# SH1_-_STM32.net
KiCad netlist of a schematic drawn in Altium Designer
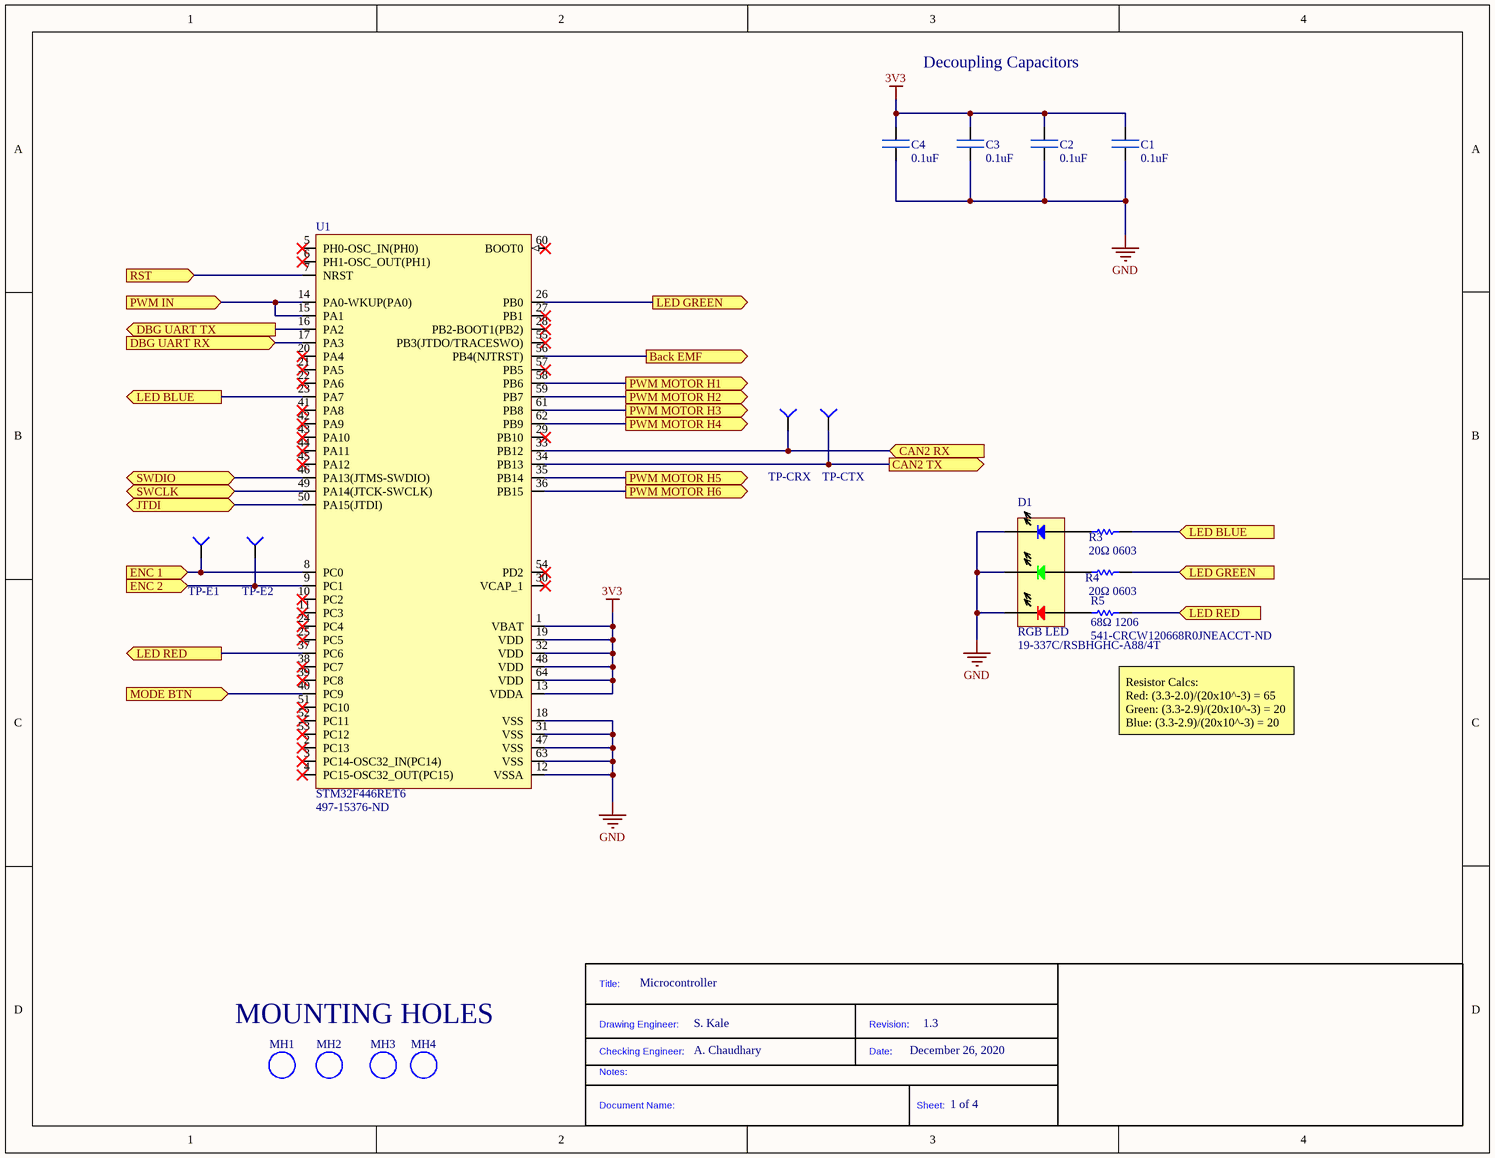
[diagram p0: SH1 - STM32.SchDoc]

(export (version "E")
  (design (tool "Eeschema 10.0.6"))
  (components
    (comp (ref "*") (value "HORNET LOGO") (libsource (lib "HORNET_MOTOR_CONTROLLER") (part "HORNET LOGO")))
    (comp (ref "C1")
      (value "0.1uF")
      (footprint "CAP0.1uF")
      (fields
        (field (name "MANUFACTURER") "Murata")
        (field (name "MANUFACTURER PART NUMBER") "GRM155R71C104KA88D")
      )
      (libsource (lib "AVRTank") (part "CAP 0.1uF"))
    )
    (comp (ref "C2")
      (value "0.1uF")
      (footprint "CAP0.1uF")
      (fields
        (field (name "MANUFACTURER") "Murata")
        (field (name "MANUFACTURER PART NUMBER") "GRM155R71C104KA88D")
      )
      (libsource (lib "AVRTank") (part "CAP 0.1uF"))
    )
    (comp (ref "C3")
      (value "0.1uF")
      (footprint "CAP0.1uF")
      (fields
        (field (name "MANUFACTURER") "Murata")
        (field (name "MANUFACTURER PART NUMBER") "GRM155R71C104KA88D")
      )
      (libsource (lib "AVRTank") (part "CAP 0.1uF"))
    )
    (comp (ref "C4")
      (value "0.1uF")
      (footprint "CAP0.1uF")
      (fields
        (field (name "MANUFACTURER") "Murata")
        (field (name "MANUFACTURER PART NUMBER") "GRM155R71C104KA88D")
      )
      (libsource (lib "AVRTank") (part "CAP 0.1uF"))
    )
    (comp (ref "D1")
      (value "RGB LED")
      (footprint "19-337C/RSBHGHC-A88/4T")
      (description "Tri Color Pcb Top View SMD Led R")
      (fields
        (field (name "MANUFACTURER") "Everlight")
        (field (name "MANUFACTURER PART NUMBER") "19-337C/RSBHGHC-A88/4T")
      )
      (libsource (lib "HORNET_MOTOR_CONTROLLER") (part "LED_RGB"))
    )
    (comp (ref "MH1")
      (value "MOUNTING HOLE")
      (footprint "MOUNTING HOLE")
      (libsource (lib "HORNET_MOTOR_CONTROLLER") (part "MOUNTING HOLE"))
    )
    (comp (ref "MH2")
      (value "MOUNTING HOLE")
      (footprint "MOUNTING HOLE")
      (libsource (lib "HORNET_MOTOR_CONTROLLER") (part "MOUNTING HOLE"))
    )
    (comp (ref "MH3")
      (value "MOUNTING HOLE")
      (footprint "MOUNTING HOLE")
      (libsource (lib "HORNET_MOTOR_CONTROLLER") (part "MOUNTING HOLE"))
    )
    (comp (ref "MH4")
      (value "MOUNTING HOLE")
      (footprint "MOUNTING HOLE")
      (libsource (lib "HORNET_MOTOR_CONTROLLER") (part "MOUNTING HOLE"))
    )
    (comp (ref "R3")
      (value "20Ω 0603")
      (footprint "SDR03EZPJ200")
      (description "Fixed Resistor, 0.1W, 20ohm, 50V, 5% +/-Tol, 200ppm/Cel, Surface Mount, 0603")
      (fields (field (name "MANUFACTURER") "Rohm") (field (name "MANUFACTURER PART NUMBER") "SDR03EZPJ200"))
      (libsource (lib "HORNET_MOTOR_CONTROLLER") (part "RES 20Ω"))
    )
    (comp (ref "R4")
      (value "20Ω 0603")
      (footprint "SDR03EZPJ200")
      (description "Fixed Resistor, 0.1W, 20ohm, 50V, 5% +/-Tol, 200ppm/Cel, Surface Mount, 0603")
      (fields (field (name "MANUFACTURER") "Rohm") (field (name "MANUFACTURER PART NUMBER") "SDR03EZPJ200"))
      (libsource (lib "HORNET_MOTOR_CONTROLLER") (part "RES 20Ω"))
    )
    (comp (ref "R5")
      (value "68Ω 1206")
      (footprint "CRCW120668R0JNEAC")
      (description "VISCRCW120668R0JNEAC Res Thick Film 1206")
      (fields
        (field (name "MANUFACTURER") "Vishay")
        (field (name "MANUFACTURER PART NUMBER") "CRCW120668R0JNEAC")
        (field (name "SUPPLIER PART NUMBER 1") "541-CRCW120668R0JNEACCT-ND")
      )
      (libsource (lib "HORNET_MOTOR_CONTROLLER") (part "RES 68Ω"))
    )
    (comp (ref "TP-CRX")
      (value "TESTPT")
      (footprint "TESTPT SQUARE")
      (libsource (lib "HORNET_MOTOR_CONTROLLER") (part "TESTPT SQUARE"))
    )
    (comp (ref "TP-CTX")
      (value "TESTPT")
      (footprint "TESTPT SQUARE")
      (libsource (lib "HORNET_MOTOR_CONTROLLER") (part "TESTPT SQUARE"))
    )
    (comp (ref "TP-E1")
      (value "TESTPT")
      (footprint "TESTPT SQUARE")
      (libsource (lib "HORNET_MOTOR_CONTROLLER") (part "TESTPT SQUARE"))
    )
    (comp (ref "TP-E2")
      (value "TESTPT")
      (footprint "TESTPT SQUARE")
      (libsource (lib "HORNET_MOTOR_CONTROLLER") (part "TESTPT SQUARE"))
    )
    (comp (ref "U1")
      (value "STM32F446RET6")
      (footprint "STM_LQFP64_N")
      (description "RISC Microcontroller, 32-Bit, FLASH, CORTEX-M4F CPU, 180MHz, CMOS, PQFP64")
      (fields
        (field (name "MANUFACTURER") "STMicroelectronics")
        (field (name "SUPPLIER PART NUMBER 1") "497-15376-ND")
      )
      (libsource (lib "HORNET_MOTOR_CONTROLLER") (part "STM32F446RET6"))
    )
  )
  (nets
    (net (code "1") (name "/Back EMF") (class "Default")
      (node (ref "U1") (pin "56") (pinfunction "PB4(NJTRST)_56") (pintype "bidirectional"))
    )
    (net (code "2") (name "/CAN2 RX") (class "Default")
      (node (ref "TP-CRX") (pin "1") (pinfunction "=value_1") (pintype "passive"))
      (node (ref "U1") (pin "33") (pinfunction "PB12_33") (pintype "bidirectional"))
    )
    (net (code "3") (name "/CAN2 TX") (class "Default")
      (node (ref "TP-CTX") (pin "1") (pinfunction "=value_1") (pintype "passive"))
      (node (ref "U1") (pin "34") (pinfunction "PB13_34") (pintype "bidirectional"))
    )
    (net (code "4") (name "/DBG UART RX") (class "Default")
      (node (ref "U1") (pin "17") (pinfunction "PA3_17") (pintype "bidirectional"))
    )
    (net (code "5") (name "/DBG UART TX") (class "Default")
      (node (ref "U1") (pin "16") (pinfunction "PA2_16") (pintype "bidirectional"))
    )
    (net (code "6") (name "/ENC 1") (class "Default")
      (node (ref "TP-E1") (pin "1") (pinfunction "=value_1") (pintype "passive"))
      (node (ref "U1") (pin "8") (pinfunction "PC0_8") (pintype "bidirectional"))
    )
    (net (code "7") (name "/ENC 2") (class "Default")
      (node (ref "TP-E2") (pin "1") (pinfunction "=value_1") (pintype "passive"))
      (node (ref "U1") (pin "9") (pinfunction "PC1_9") (pintype "bidirectional"))
    )
    (net (code "8") (name "/JTDI") (class "Default")
      (node (ref "U1") (pin "50") (pinfunction "PA15(JTDI)_50") (pintype "bidirectional"))
    )
    (net (code "9") (name "/LED BLUE") (class "Default")
      (node (ref "R3") (pin "2") (pinfunction "2_2") (pintype "passive"))
      (node (ref "U1") (pin "23") (pinfunction "PA7_23") (pintype "bidirectional"))
    )
    (net (code "10") (name "/LED GREEN") (class "Default")
      (node (ref "R4") (pin "2") (pinfunction "2_2") (pintype "passive"))
      (node (ref "U1") (pin "26") (pinfunction "PB0_26") (pintype "bidirectional"))
    )
    (net (code "11") (name "/LED RED") (class "Default")
      (node (ref "R5") (pin "2") (pinfunction "2_2") (pintype "passive"))
      (node (ref "U1") (pin "37") (pinfunction "PC6_37") (pintype "bidirectional"))
    )
    (net (code "12") (name "/MODE BTN") (class "Default")
      (node (ref "U1") (pin "40") (pinfunction "PC9_40") (pintype "bidirectional"))
    )
    (net (code "13") (name "/PWM IN") (class "Default")
      (node (ref "U1") (pin "14") (pinfunction "PA0-WKUP(PA0)_14") (pintype "bidirectional"))
      (node (ref "U1") (pin "15") (pinfunction "PA1_15") (pintype "bidirectional"))
    )
    (net (code "14") (name "/PWM MOTOR H1") (class "Default")
      (node (ref "U1") (pin "58") (pinfunction "PB6_58") (pintype "bidirectional"))
    )
    (net (code "15") (name "/PWM MOTOR H2") (class "Default")
      (node (ref "U1") (pin "59") (pinfunction "PB7_59") (pintype "bidirectional"))
    )
    (net (code "16") (name "/PWM MOTOR H3") (class "Default")
      (node (ref "U1") (pin "61") (pinfunction "PB8_61") (pintype "bidirectional"))
    )
    (net (code "17") (name "/PWM MOTOR H4") (class "Default")
      (node (ref "U1") (pin "62") (pinfunction "PB9_62") (pintype "bidirectional"))
    )
    (net (code "18") (name "/PWM MOTOR H5") (class "Default")
      (node (ref "U1") (pin "35") (pinfunction "PB14_35") (pintype "bidirectional"))
    )
    (net (code "19") (name "/PWM MOTOR H6") (class "Default")
      (node (ref "U1") (pin "36") (pinfunction "PB15_36") (pintype "bidirectional"))
    )
    (net (code "20") (name "/RST") (class "Default")
      (node (ref "U1") (pin "7") (pinfunction "NRST_7") (pintype "bidirectional"))
    )
    (net (code "21") (name "/SWCLK") (class "Default")
      (node (ref "U1") (pin "49") (pinfunction "PA14(JTCK-SWCLK)_49") (pintype "bidirectional"))
    )
    (net (code "22") (name "/SWDIO") (class "Default")
      (node (ref "U1") (pin "46") (pinfunction "PA13(JTMS-SWDIO)_46") (pintype "bidirectional"))
    )
    (net (code "23") (name "3V3") (class "Default")
      (node (ref "C1") (pin "2") (pinfunction "08_2") (pintype "passive"))
      (node (ref "C2") (pin "2") (pinfunction "08_2") (pintype "passive"))
      (node (ref "C3") (pin "2") (pinfunction "08_2") (pintype "passive"))
      (node (ref "C4") (pin "2") (pinfunction "08_2") (pintype "passive"))
      (node (ref "U1") (pin "1") (pinfunction "VBAT_1") (pintype "power_in"))
      (node (ref "U1") (pin "13") (pinfunction "VDDA_13") (pintype "power_in"))
      (node (ref "U1") (pin "19") (pinfunction "VDD_19") (pintype "power_in"))
      (node (ref "U1") (pin "32") (pinfunction "VDD_32") (pintype "power_in"))
      (node (ref "U1") (pin "48") (pinfunction "VDD_48") (pintype "power_in"))
      (node (ref "U1") (pin "64") (pinfunction "VDD_64") (pintype "power_in"))
    )
    (net (code "24") (name "GND") (class "Default")
      (node (ref "C1") (pin "1") (pintype "passive"))
      (node (ref "C2") (pin "1") (pintype "passive"))
      (node (ref "C3") (pin "1") (pintype "passive"))
      (node (ref "C4") (pin "1") (pintype "passive"))
      (node (ref "D1") (pin "1") (pinfunction "GREEN_-_1") (pintype "passive"))
      (node (ref "D1") (pin "3") (pinfunction "RED_-_3") (pintype "passive"))
      (node (ref "D1") (pin "5") (pinfunction "BLUE_-_5") (pintype "passive"))
      (node (ref "U1") (pin "12") (pinfunction "VSSA_12") (pintype "power_in"))
      (node (ref "U1") (pin "18") (pinfunction "VSS_18") (pintype "power_in"))
      (node (ref "U1") (pin "31") (pinfunction "VSS_31") (pintype "power_in"))
      (node (ref "U1") (pin "47") (pinfunction "VSS_47") (pintype "power_in"))
      (node (ref "U1") (pin "63") (pinfunction "VSS_63") (pintype "power_in"))
    )
    (net (code "25") (name "Net-(D1-Blue_+)") (class "Default")
      (node (ref "D1") (pin "6") (pinfunction "Blue_+_6") (pintype "passive"))
      (node (ref "R3") (pin "1") (pinfunction "1_1") (pintype "passive"))
    )
    (net (code "26") (name "Net-(D1-Green_+)") (class "Default")
      (node (ref "D1") (pin "2") (pinfunction "Green_+_2") (pintype "passive"))
      (node (ref "R4") (pin "1") (pinfunction "1_1") (pintype "passive"))
    )
    (net (code "27") (name "Net-(D1-Red_+)") (class "Default")
      (node (ref "D1") (pin "4") (pinfunction "Red_+_4") (pintype "passive"))
      (node (ref "R5") (pin "1") (pinfunction "1_1") (pintype "passive"))
    )
    (net (code "28") (name "unconnected-(U1-BOOT0-Pad60)") (class "Default")
      (node (ref "U1") (pin "60") (pinfunction "BOOT0_60") (pintype "input+no_connect"))
    )
    (net (code "29") (name "unconnected-(U1-PA4-Pad20)") (class "Default")
      (node (ref "U1") (pin "20") (pinfunction "PA4_20") (pintype "bidirectional+no_connect"))
    )
    (net (code "30") (name "unconnected-(U1-PA5-Pad21)") (class "Default")
      (node (ref "U1") (pin "21") (pinfunction "PA5_21") (pintype "bidirectional+no_connect"))
    )
    (net (code "31") (name "unconnected-(U1-PA6-Pad22)") (class "Default")
      (node (ref "U1") (pin "22") (pinfunction "PA6_22") (pintype "bidirectional+no_connect"))
    )
    (net (code "32") (name "unconnected-(U1-PA8-Pad41)") (class "Default")
      (node (ref "U1") (pin "41") (pinfunction "PA8_41") (pintype "bidirectional+no_connect"))
    )
    (net (code "33") (name "unconnected-(U1-PA9-Pad42)") (class "Default")
      (node (ref "U1") (pin "42") (pinfunction "PA9_42") (pintype "bidirectional+no_connect"))
    )
    (net (code "34") (name "unconnected-(U1-PA10-Pad43)") (class "Default")
      (node (ref "U1") (pin "43") (pinfunction "PA10_43") (pintype "bidirectional+no_connect"))
    )
    (net (code "35") (name "unconnected-(U1-PA11-Pad44)") (class "Default")
      (node (ref "U1") (pin "44") (pinfunction "PA11_44") (pintype "bidirectional+no_connect"))
    )
    (net (code "36") (name "unconnected-(U1-PA12-Pad45)") (class "Default")
      (node (ref "U1") (pin "45") (pinfunction "PA12_45") (pintype "bidirectional+no_connect"))
    )
    (net (code "37") (name "unconnected-(U1-PB1-Pad27)") (class "Default")
      (node (ref "U1") (pin "27") (pinfunction "PB1_27") (pintype "bidirectional+no_connect"))
    )
    (net (code "38") (name "unconnected-(U1-PB2-BOOT1(PB2)-Pad28)") (class "Default")
      (node (ref "U1") (pin "28") (pinfunction "PB2-BOOT1(PB2)_28") (pintype "bidirectional+no_connect"))
    )
    (net (code "39") (name "unconnected-(U1-PB3(JTDO{slash}TRACESWO)-Pad55)") (class "Default")
      (node (ref "U1") (pin "55") (pinfunction "PB3(JTDO/TRACESWO)_55") (pintype "bidirectional+no_connect"))
    )
    (net (code "40") (name "unconnected-(U1-PB5-Pad57)") (class "Default")
      (node (ref "U1") (pin "57") (pinfunction "PB5_57") (pintype "bidirectional+no_connect"))
    )
    (net (code "41") (name "unconnected-(U1-PB10-Pad29)") (class "Default")
      (node (ref "U1") (pin "29") (pinfunction "PB10_29") (pintype "bidirectional+no_connect"))
    )
    (net (code "42") (name "unconnected-(U1-PC2-Pad10)") (class "Default")
      (node (ref "U1") (pin "10") (pinfunction "PC2_10") (pintype "bidirectional+no_connect"))
    )
    (net (code "43") (name "unconnected-(U1-PC3-Pad11)") (class "Default")
      (node (ref "U1") (pin "11") (pinfunction "PC3_11") (pintype "bidirectional+no_connect"))
    )
    (net (code "44") (name "unconnected-(U1-PC4-Pad24)") (class "Default")
      (node (ref "U1") (pin "24") (pinfunction "PC4_24") (pintype "bidirectional+no_connect"))
    )
    (net (code "45") (name "unconnected-(U1-PC5-Pad25)") (class "Default")
      (node (ref "U1") (pin "25") (pinfunction "PC5_25") (pintype "bidirectional+no_connect"))
    )
    (net (code "46") (name "unconnected-(U1-PC7-Pad38)") (class "Default")
      (node (ref "U1") (pin "38") (pinfunction "PC7_38") (pintype "bidirectional+no_connect"))
    )
    (net (code "47") (name "unconnected-(U1-PC8-Pad39)") (class "Default")
      (node (ref "U1") (pin "39") (pinfunction "PC8_39") (pintype "bidirectional+no_connect"))
    )
    (net (code "48") (name "unconnected-(U1-PC10-Pad51)") (class "Default")
      (node (ref "U1") (pin "51") (pinfunction "PC10_51") (pintype "bidirectional+no_connect"))
    )
    (net (code "49") (name "unconnected-(U1-PC11-Pad52)") (class "Default")
      (node (ref "U1") (pin "52") (pinfunction "PC11_52") (pintype "bidirectional+no_connect"))
    )
    (net (code "50") (name "unconnected-(U1-PC12-Pad53)") (class "Default")
      (node (ref "U1") (pin "53") (pinfunction "PC12_53") (pintype "bidirectional+no_connect"))
    )
    (net (code "51") (name "unconnected-(U1-PC13-Pad2)") (class "Default")
      (node (ref "U1") (pin "2") (pinfunction "PC13_2") (pintype "bidirectional+no_connect"))
    )
    (net (code "52") (name "unconnected-(U1-PC14-OSC32_IN(PC14)-Pad3)") (class "Default")
      (node (ref "U1") (pin "3") (pinfunction "PC14-OSC32_IN(PC14)_3") (pintype "bidirectional+no_connect"))
    )
    (net (code "53") (name "unconnected-(U1-PC15-OSC32_OUT(PC15)-Pad4)") (class "Default")
      (node (ref "U1") (pin "4") (pinfunction "PC15-OSC32_OUT(PC15)_4") (pintype "bidirectional+no_connect"))
    )
    (net (code "54") (name "unconnected-(U1-PD2-Pad54)") (class "Default")
      (node (ref "U1") (pin "54") (pinfunction "PD2_54") (pintype "bidirectional+no_connect"))
    )
    (net (code "55") (name "unconnected-(U1-PH0-OSC_IN(PH0)-Pad5)") (class "Default")
      (node (ref "U1") (pin "5") (pinfunction "PH0-OSC_IN(PH0)_5") (pintype "bidirectional+no_connect"))
    )
    (net (code "56") (name "unconnected-(U1-PH1-OSC_OUT(PH1)-Pad6)") (class "Default")
      (node (ref "U1") (pin "6") (pinfunction "PH1-OSC_OUT(PH1)_6") (pintype "bidirectional+no_connect"))
    )
    (net (code "57") (name "unconnected-(U1-VCAP_1-Pad30)") (class "Default")
      (node (ref "U1") (pin "30") (pinfunction "VCAP_1_30") (pintype "passive+no_connect"))
    )
  )
)
